# FiltreFSK_TI.net
KiCad netlist of a schematic drawn in EAGLE
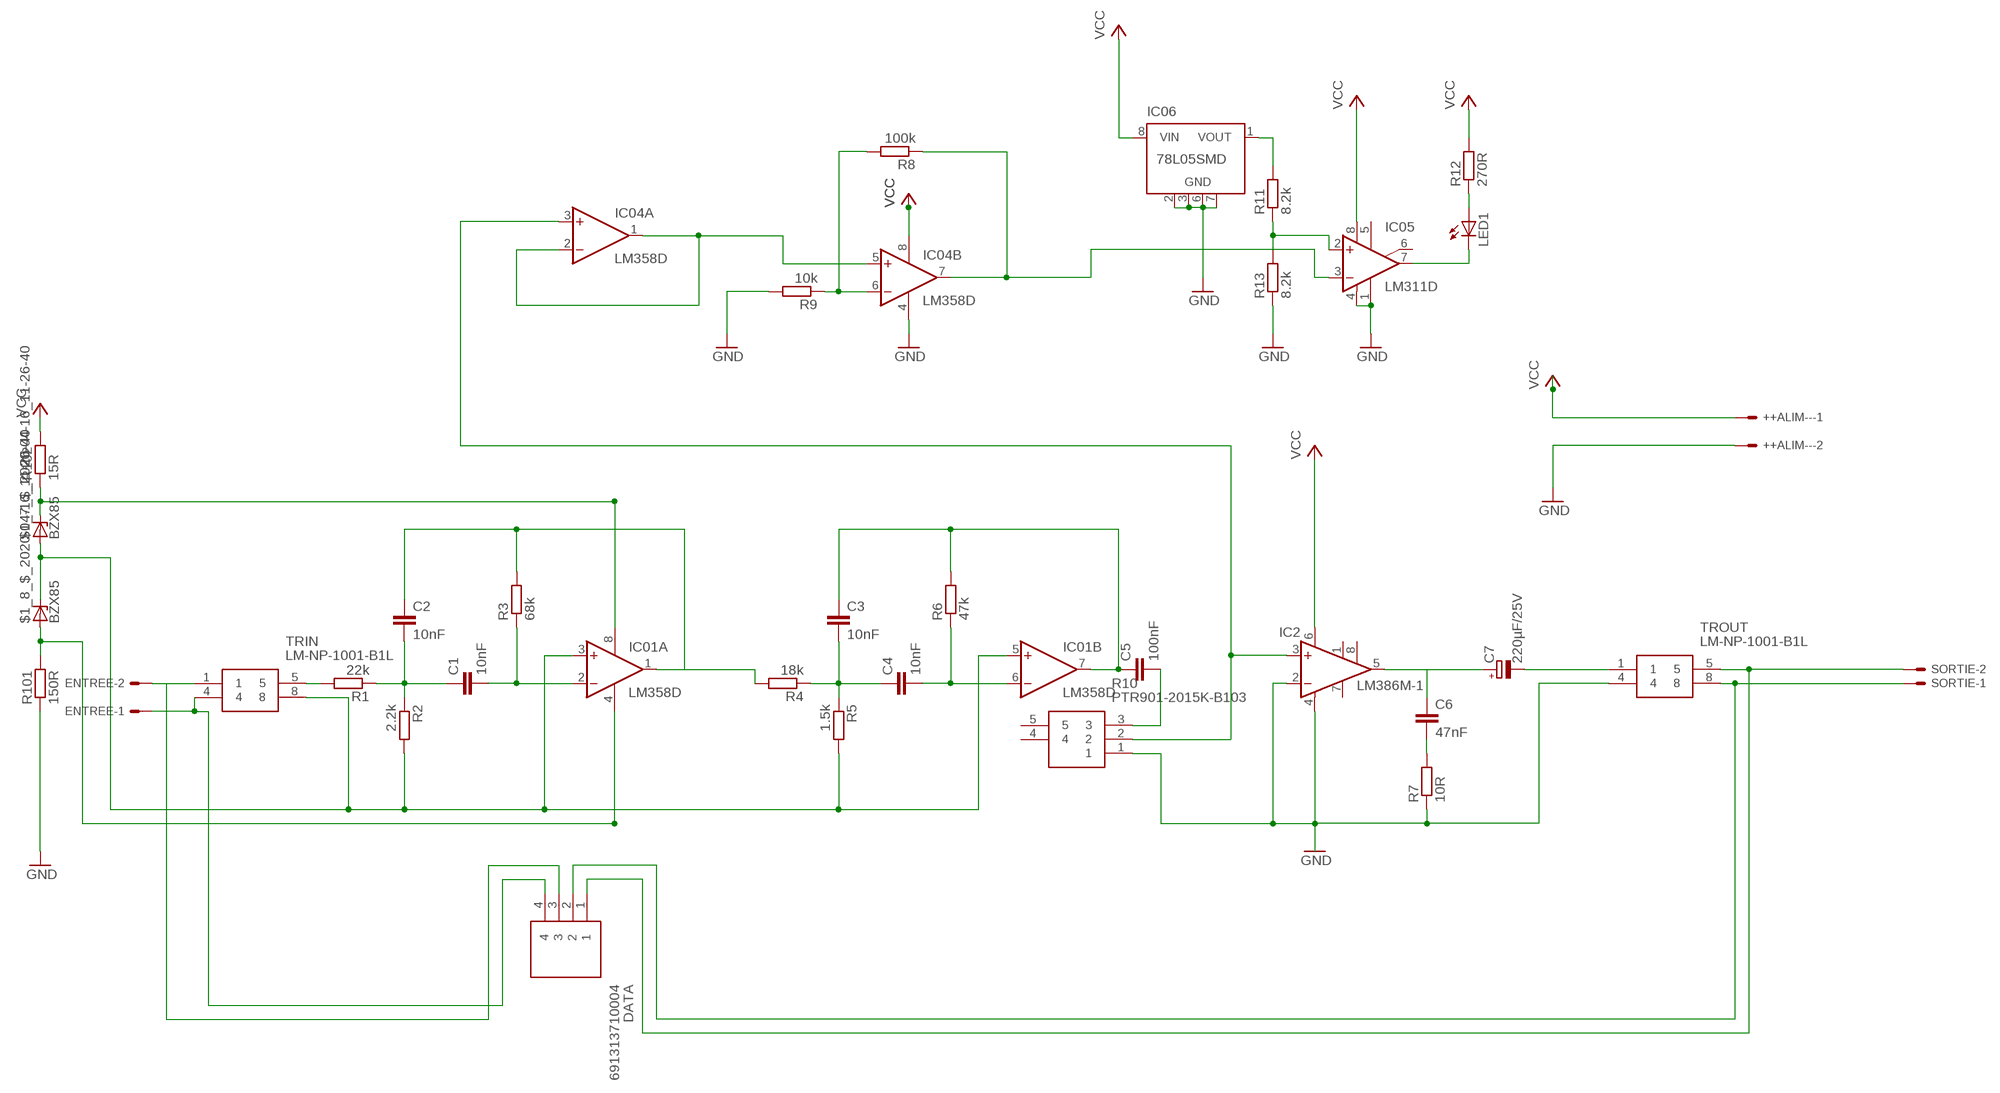
[diagram p0: schematic, sheet 1]

(export (version "E")
  (design (tool "Eeschema 10.0.6"))
  (components
    (comp (ref "$1_7_$_2020-04-16_11-26-40")
      (value "BZX85")
      (footprint "eagle-import:DO41Z10")
      (libsource (lib "eagle-import") (part "BZX85"))
    )
    (comp (ref "$1_8_$_2020-04-16_11-26-40")
      (value "BZX85")
      (footprint "eagle-import:DO41Z10")
      (libsource (lib "eagle-import") (part "BZX85"))
    )
    (comp (ref "++ALIM--")
      (value "KK-156-2")
      (footprint "eagle-import:KK-156-2")
      (libsource (lib "eagle-import") (part "KK-156-2"))
    )
    (comp (ref "C1")
      (value "10nF")
      (footprint "eagle-import:C1206")
      (libsource (lib "eagle-import") (part "C-EUC1206"))
    )
    (comp (ref "C2")
      (value "10nF")
      (footprint "eagle-import:C1206")
      (libsource (lib "eagle-import") (part "C-EUC1206"))
    )
    (comp (ref "C3")
      (value "10nF")
      (footprint "eagle-import:C1206")
      (libsource (lib "eagle-import") (part "C-EUC1206"))
    )
    (comp (ref "C4")
      (value "10nF")
      (footprint "eagle-import:C1206")
      (libsource (lib "eagle-import") (part "C-EUC1206"))
    )
    (comp (ref "C5")
      (value "100nF")
      (footprint "eagle-import:C1206")
      (libsource (lib "eagle-import") (part "C-EUC1206"))
    )
    (comp (ref "C6")
      (value "47nF")
      (footprint "eagle-import:C1206")
      (libsource (lib "eagle-import") (part "C-EUC1206"))
    )
    (comp (ref "C7")
      (value "220µF/25V")
      (footprint "eagle-import:E3,5-8")
      (libsource (lib "eagle-import") (part "CPOL-EUE3.5-8"))
    )
    (comp (ref "DATA")
      (value "691313710004")
      (footprint "eagle-import:SHDR4W140P0X500_1X4_2200X1200X")
      (fields
        (field (name "MOUSER_PART_NUMBER") "710-691313710004")
        (field (name "RS_PART_NUMBER") "8246576")
      )
      (libsource (lib "eagle-import") (part "691313710004"))
    )
    (comp (ref "ENTREE")
      (value "KK-156-2")
      (footprint "eagle-import:KK-156-2")
      (libsource (lib "eagle-import") (part "KK-156-2"))
    )
    (comp (ref "IC01")
      (value "LM358D")
      (footprint "eagle-import:SO08")
      (libsource (lib "eagle-import") (part "LM358D"))
    )
    (comp (ref "IC2")
      (value "LM386M-1")
      (footprint "eagle-import:SO08")
      (libsource (lib "eagle-import") (part "LM386?-M1"))
    )
    (comp (ref "IC04")
      (value "LM358D")
      (footprint "eagle-import:SO08")
      (libsource (lib "eagle-import") (part "LM358D"))
    )
    (comp (ref "IC05")
      (value "LM311D")
      (footprint "eagle-import:SO08")
      (libsource (lib "eagle-import") (part "LM311D"))
    )
    (comp (ref "IC06")
      (value "78L05SMD")
      (footprint "eagle-import:SO08")
      (libsource (lib "eagle-import") (part "78LSMD05"))
    )
    (comp (ref "LED1")
      (value "LED5MM")
      (footprint "eagle-import:LED5MM")
      (libsource (lib "eagle-import") (part "LED5MM"))
    )
    (comp (ref "R1")
      (value "22k")
      (footprint "eagle-import:R1206")
      (libsource (lib "eagle-import") (part "R-EU_R1206"))
    )
    (comp (ref "R2")
      (value "2.2k")
      (footprint "eagle-import:R1206")
      (libsource (lib "eagle-import") (part "R-EU_R1206"))
    )
    (comp (ref "R3")
      (value "68k")
      (footprint "eagle-import:R1206")
      (libsource (lib "eagle-import") (part "R-EU_R1206"))
    )
    (comp (ref "R4")
      (value "18k")
      (footprint "eagle-import:R1206")
      (libsource (lib "eagle-import") (part "R-EU_R1206"))
    )
    (comp (ref "R5")
      (value "1.5k")
      (footprint "eagle-import:R1206")
      (libsource (lib "eagle-import") (part "R-EU_R1206"))
    )
    (comp (ref "R6")
      (value "47k")
      (footprint "eagle-import:R1206")
      (libsource (lib "eagle-import") (part "R-EU_R1206"))
    )
    (comp (ref "R7")
      (value "10R")
      (footprint "eagle-import:R1206")
      (libsource (lib "eagle-import") (part "R-EU_R1206"))
    )
    (comp (ref "R8")
      (value "100k")
      (footprint "eagle-import:R1206")
      (libsource (lib "eagle-import") (part "R-EU_R1206"))
    )
    (comp (ref "R9")
      (value "10k")
      (footprint "eagle-import:R1206")
      (libsource (lib "eagle-import") (part "R-EU_R1206"))
    )
    (comp (ref "R10")
      (value "PTR901-2015K-B103")
      (footprint "eagle-import:PTR9012015KB103")
      (fields
        (field (name "MOUSER_PART_NUMBER") "652-PTR901-2015KB103")
        (field (name "RS_PART_NUMBER") "8275003P")
      )
      (libsource (lib "eagle-import") (part "PTR901-2015K-B103"))
    )
    (comp (ref "R11")
      (value "8.2k")
      (footprint "eagle-import:R1210")
      (libsource (lib "eagle-import") (part "R-EU_R1210"))
    )
    (comp (ref "R12")
      (value "270R")
      (footprint "eagle-import:R1206")
      (libsource (lib "eagle-import") (part "R-EU_R1206"))
    )
    (comp (ref "R13")
      (value "8.2k")
      (footprint "eagle-import:R1210")
      (libsource (lib "eagle-import") (part "R-EU_R1210"))
    )
    (comp (ref "R101")
      (value "150R")
      (footprint "eagle-import:0207_10")
      (libsource (lib "eagle-import") (part "R-EU_0207/10"))
    )
    (comp (ref "R102")
      (value "15R")
      (footprint "eagle-import:0207_10")
      (libsource (lib "eagle-import") (part "R-EU_0207/10"))
    )
    (comp (ref "SORTIE")
      (value "KK-156-2")
      (footprint "eagle-import:KK-156-2")
      (libsource (lib "eagle-import") (part "KK-156-2"))
    )
    (comp (ref "TRIN")
      (value "LM-NP-1001-B1L")
      (footprint "eagle-import:LMNP1001B1L")
      (fields
        (field (name "MOUSER_PART_NUMBER") "652-LM-NP-1001-B1L")
        (field (name "RS_PART_NUMBER") "1740620")
      )
      (libsource (lib "eagle-import") (part "LM-NP-1001-B1L"))
    )
    (comp (ref "TROUT")
      (value "LM-NP-1001-B1L")
      (footprint "eagle-import:LMNP1001B1L")
      (fields
        (field (name "MOUSER_PART_NUMBER") "652-LM-NP-1001-B1L")
        (field (name "RS_PART_NUMBER") "1740620")
      )
      (libsource (lib "eagle-import") (part "LM-NP-1001-B1L"))
    )
  )
  (nets
    (net (code "1") (name "GND") (class "Default")
      (node (ref "++ALIM--") (pin "2") (pinfunction "S_2") (pintype "passive"))
      (node (ref "IC04") (pin "4") (pinfunction "V-_4") (pintype "power_in"))
      (node (ref "IC05") (pin "1") (pinfunction "GND_1") (pintype "passive"))
      (node (ref "IC05") (pin "4") (pinfunction "V-_4") (pintype "power_in"))
      (node (ref "IC06") (pin "2") (pinfunction "GND_2") (pintype "power_in"))
      (node (ref "IC06") (pin "3") (pinfunction "GND_3") (pintype "power_in"))
      (node (ref "IC06") (pin "6") (pinfunction "GND_6") (pintype "power_in"))
      (node (ref "IC06") (pin "7") (pinfunction "GND_7") (pintype "power_in"))
      (node (ref "IC2") (pin "2") (pinfunction "-IN_2") (pintype "input"))
      (node (ref "IC2") (pin "4") (pinfunction "GND_4") (pintype "power_in"))
      (node (ref "R10") (pin "1") (pinfunction "1_1") (pintype "bidirectional"))
      (node (ref "R101") (pin "1") (pinfunction "1_1") (pintype "passive"))
      (node (ref "R13") (pin "1") (pinfunction "1_1") (pintype "passive"))
      (node (ref "R7") (pin "1") (pinfunction "1_1") (pintype "passive"))
      (node (ref "R9") (pin "2") (pinfunction "2_2") (pintype "passive"))
      (node (ref "TROUT") (pin "4") (pinfunction "4_4") (pintype "bidirectional"))
    )
    (net (code "2") (name "Net-(C1-Pad1)") (class "Default")
      (node (ref "C1") (pin "1") (pinfunction "1_1") (pintype "passive"))
      (node (ref "C2") (pin "2") (pinfunction "2_2") (pintype "passive"))
      (node (ref "R1") (pin "1") (pinfunction "1_1") (pintype "passive"))
      (node (ref "R2") (pin "1") (pinfunction "1_1") (pintype "passive"))
    )
    (net (code "3") (name "Net-(C3-Pad2)") (class "Default")
      (node (ref "C3") (pin "2") (pinfunction "2_2") (pintype "passive"))
      (node (ref "C4") (pin "1") (pinfunction "1_1") (pintype "passive"))
      (node (ref "R4") (pin "1") (pinfunction "1_1") (pintype "passive"))
      (node (ref "R5") (pin "1") (pinfunction "1_1") (pintype "passive"))
    )
    (net (code "4") (name "Net-(C5-Pad2)") (class "Default")
      (node (ref "C5") (pin "2") (pinfunction "2_2") (pintype "passive"))
      (node (ref "R10") (pin "3") (pinfunction "3_3") (pintype "bidirectional"))
    )
    (net (code "5") (name "Net-(C6-Pad2)") (class "Default")
      (node (ref "C6") (pin "2") (pinfunction "2_2") (pintype "passive"))
      (node (ref "R7") (pin "2") (pinfunction "2_2") (pintype "passive"))
    )
    (net (code "6") (name "Net-(C7-Pad-)") (class "Default")
      (node (ref "C7") (pin "-") (pinfunction "-_-") (pintype "passive"))
      (node (ref "TROUT") (pin "1") (pinfunction "1_1") (pintype "bidirectional"))
    )
    (net (code "7") (name "Net-(ENTREEA-S)") (class "Default")
      (node (ref "DATA") (pin "4") (pinfunction "4_4") (pintype "bidirectional"))
      (node (ref "ENTREE") (pin "1") (pinfunction "S_1") (pintype "passive"))
      (node (ref "TRIN") (pin "4") (pinfunction "4_4") (pintype "bidirectional"))
    )
    (net (code "8") (name "Net-(ENTREEB-S)") (class "Default")
      (node (ref "DATA") (pin "3") (pinfunction "3_3") (pintype "bidirectional"))
      (node (ref "ENTREE") (pin "2") (pinfunction "S_2") (pintype "passive"))
      (node (ref "TRIN") (pin "1") (pinfunction "1_1") (pintype "bidirectional"))
    )
    (net (code "9") (name "Net-(IC01A-+IN)") (class "Default")
      (node (ref "$1_7_$_2020-04-16_11-26-40") (pin "A") (pinfunction "A_A") (pintype "passive"))
      (node (ref "$1_8_$_2020-04-16_11-26-40") (pin "C") (pinfunction "C_C") (pintype "passive"))
      (node (ref "IC01") (pin "3") (pinfunction "+IN_3") (pintype "input"))
      (node (ref "IC01") (pin "5") (pinfunction "+IN_5") (pintype "input"))
      (node (ref "R2") (pin "2") (pinfunction "2_2") (pintype "passive"))
      (node (ref "R5") (pin "2") (pinfunction "2_2") (pintype "passive"))
      (node (ref "TRIN") (pin "8") (pinfunction "8_8") (pintype "bidirectional"))
    )
    (net (code "10") (name "Net-(IC01A--IN)") (class "Default")
      (node (ref "C1") (pin "2") (pinfunction "2_2") (pintype "passive"))
      (node (ref "IC01") (pin "2") (pinfunction "-IN_2") (pintype "input"))
      (node (ref "R3") (pin "1") (pinfunction "1_1") (pintype "passive"))
    )
    (net (code "11") (name "Net-(IC01A-OUT)") (class "Default")
      (node (ref "C2") (pin "1") (pinfunction "1_1") (pintype "passive"))
      (node (ref "IC01") (pin "1") (pinfunction "OUT_1") (pintype "output"))
      (node (ref "R3") (pin "2") (pinfunction "2_2") (pintype "passive"))
      (node (ref "R4") (pin "2") (pinfunction "2_2") (pintype "passive"))
    )
    (net (code "12") (name "Net-(IC01B--IN)") (class "Default")
      (node (ref "C4") (pin "2") (pinfunction "2_2") (pintype "passive"))
      (node (ref "IC01") (pin "6") (pinfunction "-IN_6") (pintype "input"))
      (node (ref "R6") (pin "1") (pinfunction "1_1") (pintype "passive"))
    )
    (net (code "13") (name "Net-(IC01B-OUT)") (class "Default")
      (node (ref "C3") (pin "1") (pinfunction "1_1") (pintype "passive"))
      (node (ref "C5") (pin "1") (pinfunction "1_1") (pintype "passive"))
      (node (ref "IC01") (pin "7") (pinfunction "OUT_7") (pintype "output"))
      (node (ref "R6") (pin "2") (pinfunction "2_2") (pintype "passive"))
    )
    (net (code "14") (name "Net-(IC01C-V+)") (class "Default")
      (node (ref "$1_7_$_2020-04-16_11-26-40") (pin "C") (pinfunction "C_C") (pintype "passive"))
      (node (ref "IC01") (pin "8") (pinfunction "V+_8") (pintype "power_in"))
      (node (ref "R102") (pin "1") (pinfunction "1_1") (pintype "passive"))
    )
    (net (code "15") (name "Net-(IC01C-V-)") (class "Default")
      (node (ref "$1_8_$_2020-04-16_11-26-40") (pin "A") (pinfunction "A_A") (pintype "passive"))
      (node (ref "IC01") (pin "4") (pinfunction "V-_4") (pintype "power_in"))
      (node (ref "R101") (pin "2") (pinfunction "2_2") (pintype "passive"))
    )
    (net (code "16") (name "Net-(IC2-OUT)") (class "Default")
      (node (ref "C6") (pin "1") (pinfunction "1_1") (pintype "passive"))
      (node (ref "C7") (pin "+") (pinfunction "+_+") (pintype "passive"))
      (node (ref "IC2") (pin "5") (pinfunction "OUT_5") (pintype "output"))
    )
    (net (code "17") (name "Net-(IC04A-+IN)") (class "Default")
      (node (ref "IC04") (pin "3") (pinfunction "+IN_3") (pintype "input"))
      (node (ref "IC2") (pin "3") (pinfunction "+IN_3") (pintype "input"))
      (node (ref "R10") (pin "2") (pinfunction "2_2") (pintype "bidirectional"))
    )
    (net (code "18") (name "Net-(IC04A--IN)") (class "Default")
      (node (ref "IC04") (pin "1") (pinfunction "OUT_1") (pintype "output"))
      (node (ref "IC04") (pin "2") (pinfunction "-IN_2") (pintype "input"))
      (node (ref "IC04") (pin "5") (pinfunction "+IN_5") (pintype "input"))
    )
    (net (code "19") (name "Net-(IC04B--IN)") (class "Default")
      (node (ref "IC04") (pin "6") (pinfunction "-IN_6") (pintype "input"))
      (node (ref "R8") (pin "2") (pinfunction "2_2") (pintype "passive"))
      (node (ref "R9") (pin "1") (pinfunction "1_1") (pintype "passive"))
    )
    (net (code "20") (name "Net-(IC04B-OUT)") (class "Default")
      (node (ref "IC04") (pin "7") (pinfunction "OUT_7") (pintype "output"))
      (node (ref "IC05") (pin "3") (pinfunction "-IN_3") (pintype "input"))
      (node (ref "R8") (pin "1") (pinfunction "1_1") (pintype "passive"))
    )
    (net (code "21") (name "Net-(IC05-+IN)") (class "Default")
      (node (ref "IC05") (pin "2") (pinfunction "+IN_2") (pintype "input"))
      (node (ref "R11") (pin "1") (pinfunction "1_1") (pintype "passive"))
      (node (ref "R13") (pin "2") (pinfunction "2_2") (pintype "passive"))
    )
    (net (code "22") (name "Net-(IC05-OUT)") (class "Default")
      (node (ref "IC05") (pin "7") (pinfunction "OUT_7") (pintype "output"))
      (node (ref "LED1") (pin "K") (pinfunction "C_K") (pintype "passive"))
    )
    (net (code "23") (name "Net-(IC06A-VOUT)") (class "Default")
      (node (ref "IC06") (pin "1") (pinfunction "VOUT_1") (pintype "output"))
      (node (ref "R11") (pin "2") (pinfunction "2_2") (pintype "passive"))
    )
    (net (code "24") (name "Net-(LED1-PadA)") (class "Default")
      (node (ref "LED1") (pin "A") (pinfunction "A_A") (pintype "passive"))
      (node (ref "R12") (pin "1") (pinfunction "1_1") (pintype "passive"))
    )
    (net (code "25") (name "Net-(R1-Pad2)") (class "Default")
      (node (ref "R1") (pin "2") (pinfunction "2_2") (pintype "passive"))
      (node (ref "TRIN") (pin "5") (pinfunction "5_5") (pintype "bidirectional"))
    )
    (net (code "26") (name "Net-(SORTIEA-S)") (class "Default")
      (node (ref "DATA") (pin "2") (pinfunction "2_2") (pintype "bidirectional"))
      (node (ref "SORTIE") (pin "1") (pinfunction "S_1") (pintype "passive"))
      (node (ref "TROUT") (pin "8") (pinfunction "8_8") (pintype "bidirectional"))
    )
    (net (code "27") (name "Net-(SORTIEB-S)") (class "Default")
      (node (ref "DATA") (pin "1") (pinfunction "1_1") (pintype "bidirectional"))
      (node (ref "SORTIE") (pin "2") (pinfunction "S_2") (pintype "passive"))
      (node (ref "TROUT") (pin "5") (pinfunction "5_5") (pintype "bidirectional"))
    )
    (net (code "28") (name "VCC") (class "Default")
      (node (ref "++ALIM--") (pin "1") (pinfunction "S_1") (pintype "passive"))
      (node (ref "IC04") (pin "8") (pinfunction "V+_8") (pintype "power_in"))
      (node (ref "IC05") (pin "8") (pinfunction "V+_8") (pintype "power_in"))
      (node (ref "IC06") (pin "8") (pinfunction "VIN_8") (pintype "passive"))
      (node (ref "IC2") (pin "6") (pinfunction "VS_6") (pintype "power_in"))
      (node (ref "R102") (pin "2") (pinfunction "2_2") (pintype "passive"))
      (node (ref "R12") (pin "2") (pinfunction "2_2") (pintype "passive"))
    )
    (net (code "29") (name "unconnected-(IC2-BYPASS-Pad7)") (class "Default")
      (node (ref "IC2") (pin "7") (pinfunction "BYPASS_7") (pintype "passive"))
    )
    (net (code "30") (name "unconnected-(IC2-GAIN-Pad1)") (class "Default")
      (node (ref "IC2") (pin "1") (pinfunction "GAIN_1") (pintype "passive"))
    )
    (net (code "31") (name "unconnected-(IC2-GAIN-Pad8)") (class "Default")
      (node (ref "IC2") (pin "8") (pinfunction "GAIN_8") (pintype "passive"))
    )
    (net (code "32") (name "unconnected-(IC05-ON-Pad5)") (class "Default")
      (node (ref "IC05") (pin "5") (pinfunction "ON_5") (pintype "passive"))
    )
    (net (code "33") (name "unconnected-(IC05-ON{slash}STR-Pad6)") (class "Default")
      (node (ref "IC05") (pin "6") (pinfunction "ON/STR_6") (pintype "passive"))
    )
    (net (code "34") (name "unconnected-(R10-Pad4)") (class "Default")
      (node (ref "R10") (pin "4") (pinfunction "4_4") (pintype "bidirectional"))
    )
    (net (code "35") (name "unconnected-(R10-Pad5)") (class "Default")
      (node (ref "R10") (pin "5") (pinfunction "5_5") (pintype "bidirectional"))
    )
  )
)
